# IPMI.net
KiCad netlist of a schematic drawn in Altium Designer
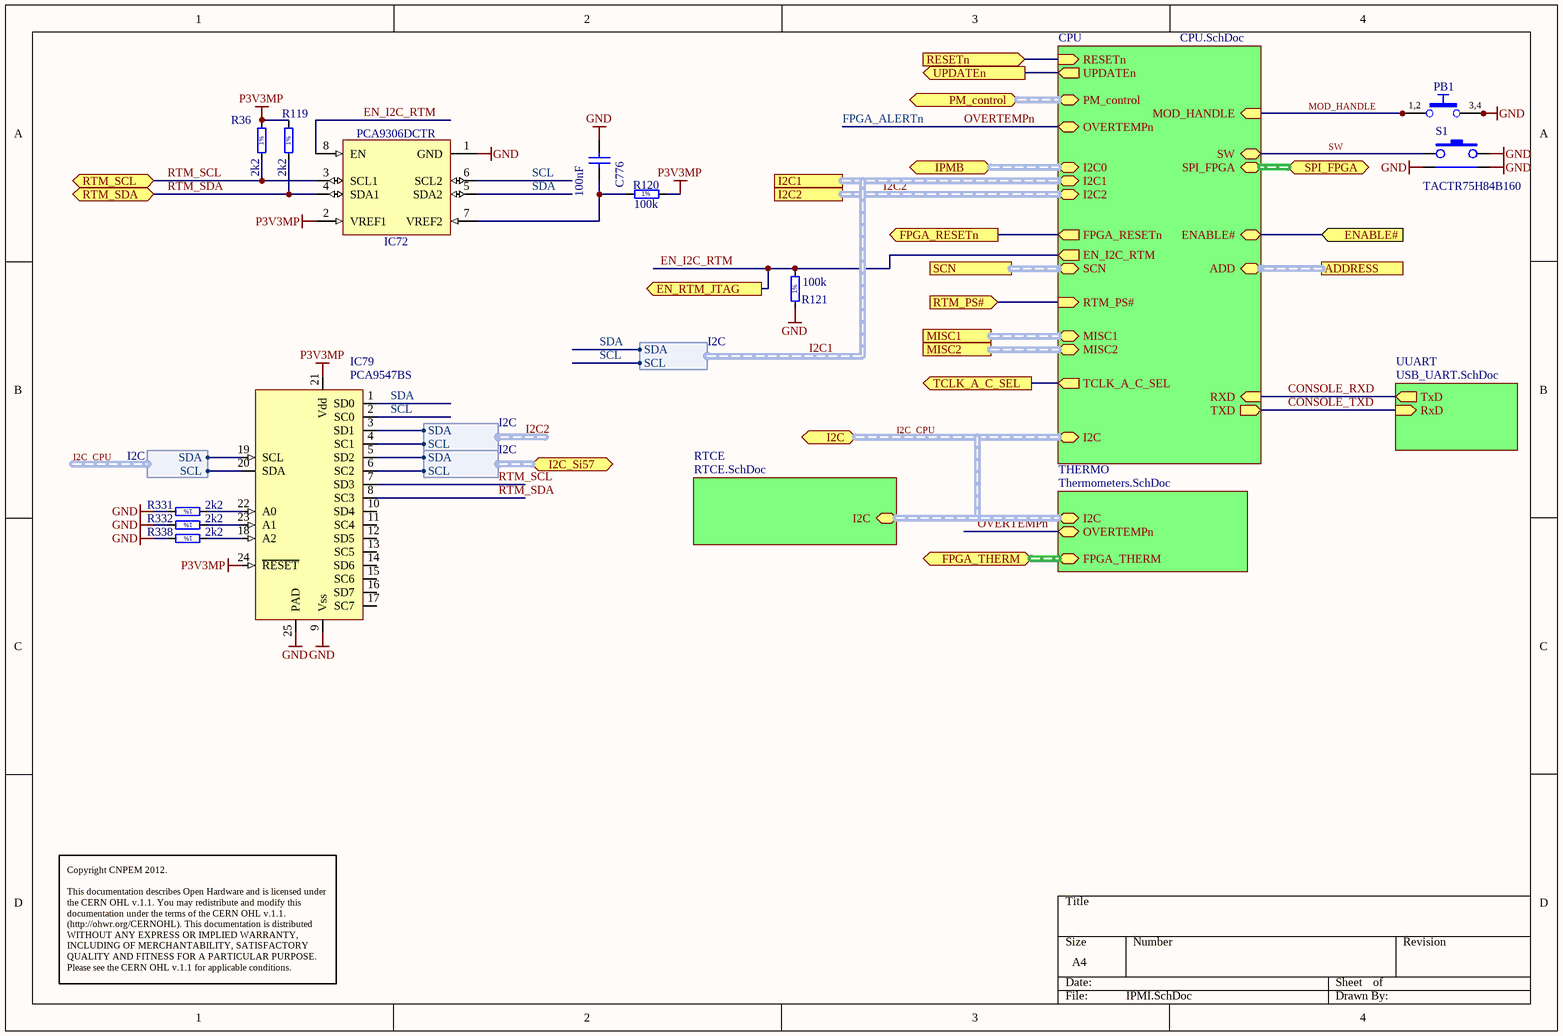
[diagram p0: IPMI.SchDoc]

(export (version "E")
  (design (tool "Eeschema 10.0.6"))
  (components
    (comp (ref "C776")
      (value "100nF")
      (footprint "CAPC0603X33N")
      (description "Non-polarised capacitor")
      (fields
        (field (name "PART NUMBER") "CC0201_100NF_6.3V_10%_X5R")
        (field (name "VOLTAGE") "6.3V")
        (field (name "AUTHOR") "CERN DEM JLC")
      )
      (libsource (lib "Capacitors") (part "Capacitor - non polarized"))
    )
    (comp (ref "IC72")
      (value "PCA9306DCTR")
      (footprint "SOP65P400X130-8N")
      (description "Dual Bidirectional I2C Bus And SMBus Voltage-Level Translator")
      (fields (field (name "MANUFACTURER") "TEXAS INSTRUMENTS") (field (name "AUTHOR") "CERN DEM JLC"))
      (libsource (lib "ICs And Semiconductors") (part "PCA9306DC"))
    )
    (comp (ref "IC79")
      (value "PCA9547BS")
      (footprint "HVQFN24")
      (description "8-channel I2C-bus multiplexer with reset")
      (libsource (lib "LIBRARY_SCH") (part "IIC_MUX_PCA9547"))
    )
    (comp (ref "PB1")
      (value "Push Button")
      (footprint "SW_C&K_HDT0001")
      (description "Push-Button Switch SPDT")
      (fields
        (field (name "PART NUMBER") "SW_C&K_HDT0001")
        (field (name "MANUFACTURER") "C&K")
        (field (name "AUTHOR") "CERN DEM JLC")
      )
      (libsource (lib "Eletro-mechanical") (part "PB SPST 12NO-34NO"))
    )
    (comp (ref "R36")
      (value "2k2")
      (footprint "RESC1005X40N")
      (description "Resistor - 1%")
      (fields
        (field (name "PART NUMBER") "R0402_2K2_1%_0.0625W_100PPM")
        (field (name "POWER") "0.0625W")
        (field (name "AUTHOR") "CERN DEM JLC")
      )
      (libsource (lib "Resistors") (part "Resistor - 1%"))
    )
    (comp (ref "R119")
      (value "2k2")
      (footprint "RESC1005X40N")
      (description "Resistor - 1%")
      (fields
        (field (name "PART NUMBER") "R0402_2K2_1%_0.0625W_100PPM")
        (field (name "POWER") "0.0625W")
        (field (name "AUTHOR") "CERN DEM JLC")
      )
      (libsource (lib "Resistors") (part "Resistor - 1%"))
    )
    (comp (ref "R120")
      (value "100k")
      (footprint "RESC1005X40N")
      (description "Resistor - 1%")
      (fields
        (field (name "PART NUMBER") "R0402_100K_1%_0.0625W_100PPM")
        (field (name "POWER") "0.0625W")
        (field (name "AUTHOR") "CERN DEM JLC")
      )
      (libsource (lib "Resistors") (part "Resistor - 1%"))
    )
    (comp (ref "R121")
      (value "100k")
      (footprint "RESC1005X40N")
      (description "Resistor - 1%")
      (fields
        (field (name "PART NUMBER") "R0402_100K_1%_0.0625W_100PPM")
        (field (name "POWER") "0.0625W")
        (field (name "AUTHOR") "CERN DEM JLC")
      )
      (libsource (lib "Resistors") (part "Resistor - 1%"))
    )
    (comp (ref "R331")
      (value "2k2")
      (footprint "RESC1005X40N")
      (description "Resistor - 1%")
      (fields
        (field (name "PART NUMBER") "R0402_2K2_1%_0.0625W_100PPM")
        (field (name "POWER") "0.0625W")
        (field (name "AUTHOR") "CERN DEM JLC")
      )
      (libsource (lib "Resistors") (part "Resistor - 1%"))
    )
    (comp (ref "R332")
      (value "2k2")
      (footprint "RESC1005X40N")
      (description "Resistor - 1%")
      (fields
        (field (name "PART NUMBER") "R0402_2K2_1%_0.0625W_100PPM")
        (field (name "POWER") "0.0625W")
        (field (name "AUTHOR") "CERN DEM JLC")
      )
      (libsource (lib "Resistors") (part "Resistor - 1%"))
    )
    (comp (ref "R338")
      (value "2k2")
      (footprint "RESC1005X40N")
      (description "Resistor - 1%")
      (fields
        (field (name "PART NUMBER") "R0402_2K2_1%_0.0625W_100PPM")
        (field (name "POWER") "0.0625W")
        (field (name "AUTHOR") "CERN DEM JLC")
      )
      (libsource (lib "Resistors") (part "Resistor - 1%"))
    )
    (comp (ref "S1")
      (value "TACTR75H84B160")
      (footprint "PB_ALPS_SKHHLQA010")
      (description "Push button")
      (libsource (lib "LIBRARY_SCH") (part "SW-PB_RA_5.8mm"))
    )
  )
  (nets
    (net (code "18") (name "/EN_I2C_RTM") (class "Default")
      (node (ref "IC72") (pin "8") (pinfunction "EN_8") (pintype "input"))
      (node (ref "R121") (pin "2") (pinfunction "2_2") (pintype "passive"))
    )
    (net (code "28") (name "/MOD_HANDLE") (class "Default")
      (node (ref "PB1") (pin "1") (pinfunction "1_1") (pintype "passive"))
      (node (ref "PB1") (pin "2") (pinfunction "2_2") (pintype "passive"))
    )
    (net (code "32") (name "/RTM_SCL") (class "Default")
      (node (ref "IC72") (pin "3") (pinfunction "SCL1_3") (pintype "bidirectional"))
      (node (ref "IC79") (pin "7") (pinfunction "SD3_7") (pintype "bidirectional"))
      (node (ref "R36") (pin "1") (pinfunction "1_1") (pintype "passive"))
    )
    (net (code "33") (name "/RTM_SDA") (class "Default")
      (node (ref "IC72") (pin "4") (pinfunction "SDA1_4") (pintype "bidirectional"))
      (node (ref "IC79") (pin "8") (pinfunction "SC3_8") (pintype "bidirectional"))
      (node (ref "R119") (pin "1") (pinfunction "1_1") (pintype "passive"))
    )
    (net (code "34") (name "/SCL") (class "Default")
      (node (ref "IC72") (pin "6") (pinfunction "SCL2_6") (pintype "bidirectional"))
      (node (ref "IC79") (pin "2") (pinfunction "SC0_2") (pintype "bidirectional"))
    )
    (net (code "36") (name "/SDA") (class "Default")
      (node (ref "IC72") (pin "5") (pinfunction "SDA2_5") (pintype "bidirectional"))
      (node (ref "IC79") (pin "1") (pinfunction "SD0_1") (pintype "bidirectional"))
    )
    (net (code "38") (name "/SW") (class "Default")
      (node (ref "S1") (pin "1") (pinfunction "1_1") (pintype "passive"))
    )
    (net (code "43") (name "GND") (class "Default")
      (node (ref "C776") (pin "2") (pinfunction "2_2") (pintype "passive"))
      (node (ref "IC72") (pin "1") (pinfunction "GND_1") (pintype "power_in"))
      (node (ref "IC79") (pin "25") (pinfunction "PAD_25") (pintype "power_in"))
      (node (ref "IC79") (pin "9") (pinfunction "Vss_9") (pintype "power_in"))
      (node (ref "PB1") (pin "3") (pinfunction "3_3") (pintype "passive"))
      (node (ref "PB1") (pin "4") (pinfunction "4_4") (pintype "passive"))
      (node (ref "R121") (pin "1") (pinfunction "1_1") (pintype "passive"))
      (node (ref "R331") (pin "2") (pinfunction "2_2") (pintype "passive"))
      (node (ref "R332") (pin "2") (pinfunction "2_2") (pintype "passive"))
      (node (ref "R338") (pin "2") (pinfunction "2_2") (pintype "passive"))
      (node (ref "S1") (pin "2") (pinfunction "2_2") (pintype "passive"))
      (node (ref "S1") (pin "3") (pinfunction "3_3") (pintype "passive"))
      (node (ref "S1") (pin "4") (pinfunction "4_4") (pintype "passive"))
    )
    (net (code "44") (name "Net-(IC72-VREF2)") (class "Default")
      (node (ref "C776") (pin "1") (pinfunction "1_1") (pintype "passive"))
      (node (ref "IC72") (pin "7") (pinfunction "VREF2_7") (pintype "input"))
      (node (ref "R120") (pin "1") (pinfunction "1_1") (pintype "passive"))
    )
    (net (code "45") (name "Net-(IC79-A0)") (class "Default")
      (node (ref "IC79") (pin "22") (pinfunction "A0_22") (pintype "input"))
      (node (ref "R331") (pin "1") (pinfunction "1_1") (pintype "passive"))
    )
    (net (code "46") (name "Net-(IC79-A1)") (class "Default")
      (node (ref "IC79") (pin "23") (pinfunction "A1_23") (pintype "input"))
      (node (ref "R332") (pin "1") (pinfunction "1_1") (pintype "passive"))
    )
    (net (code "47") (name "Net-(IC79-A2)") (class "Default")
      (node (ref "IC79") (pin "18") (pinfunction "A2_18") (pintype "input"))
      (node (ref "R338") (pin "1") (pinfunction "1_1") (pintype "passive"))
    )
    (net (code "48") (name "P3V3MP") (class "Default")
      (node (ref "IC72") (pin "2") (pinfunction "VREF1_2") (pintype "input"))
      (node (ref "IC79") (pin "21") (pinfunction "Vdd_21") (pintype "power_in"))
      (node (ref "IC79") (pin "24") (pinfunction "~{RESET}_24") (pintype "input"))
      (node (ref "R119") (pin "2") (pinfunction "2_2") (pintype "passive"))
      (node (ref "R120") (pin "2") (pinfunction "2_2") (pintype "passive"))
      (node (ref "R36") (pin "2") (pinfunction "2_2") (pintype "passive"))
    )
    (net (code "49") (name "unconnected-(IC79-SC1-Pad4)") (class "Default")
      (node (ref "IC79") (pin "4") (pinfunction "SC1_4") (pintype "bidirectional"))
    )
    (net (code "50") (name "unconnected-(IC79-SC2-Pad6)") (class "Default")
      (node (ref "IC79") (pin "6") (pinfunction "SC2_6") (pintype "bidirectional"))
    )
    (net (code "51") (name "unconnected-(IC79-SC4-Pad11)") (class "Default")
      (node (ref "IC79") (pin "11") (pinfunction "SC4_11") (pintype "bidirectional"))
    )
    (net (code "52") (name "unconnected-(IC79-SC5-Pad13)") (class "Default")
      (node (ref "IC79") (pin "13") (pinfunction "SC5_13") (pintype "bidirectional"))
    )
    (net (code "53") (name "unconnected-(IC79-SC6-Pad15)") (class "Default")
      (node (ref "IC79") (pin "15") (pinfunction "SC6_15") (pintype "bidirectional"))
    )
    (net (code "54") (name "unconnected-(IC79-SC7-Pad17)") (class "Default")
      (node (ref "IC79") (pin "17") (pinfunction "SC7_17") (pintype "bidirectional"))
    )
    (net (code "55") (name "unconnected-(IC79-SCL-Pad19)") (class "Default")
      (node (ref "IC79") (pin "19") (pinfunction "SCL_19") (pintype "input"))
    )
    (net (code "56") (name "unconnected-(IC79-SD1-Pad3)") (class "Default")
      (node (ref "IC79") (pin "3") (pinfunction "SD1_3") (pintype "bidirectional"))
    )
    (net (code "57") (name "unconnected-(IC79-SD2-Pad5)") (class "Default")
      (node (ref "IC79") (pin "5") (pinfunction "SD2_5") (pintype "bidirectional"))
    )
    (net (code "58") (name "unconnected-(IC79-SD4-Pad10)") (class "Default")
      (node (ref "IC79") (pin "10") (pinfunction "SD4_10") (pintype "bidirectional"))
    )
    (net (code "59") (name "unconnected-(IC79-SD5-Pad12)") (class "Default")
      (node (ref "IC79") (pin "12") (pinfunction "SD5_12") (pintype "bidirectional"))
    )
    (net (code "60") (name "unconnected-(IC79-SD6-Pad14)") (class "Default")
      (node (ref "IC79") (pin "14") (pinfunction "SD6_14") (pintype "bidirectional"))
    )
    (net (code "61") (name "unconnected-(IC79-SD7-Pad16)") (class "Default")
      (node (ref "IC79") (pin "16") (pinfunction "SD7_16") (pintype "bidirectional"))
    )
    (net (code "62") (name "unconnected-(IC79-SDA-Pad20)") (class "Default")
      (node (ref "IC79") (pin "20") (pinfunction "SDA_20") (pintype "bidirectional"))
    )
  )
)
